# RedBot_Accelerometer.net
KiCad netlist of a schematic drawn in EAGLE
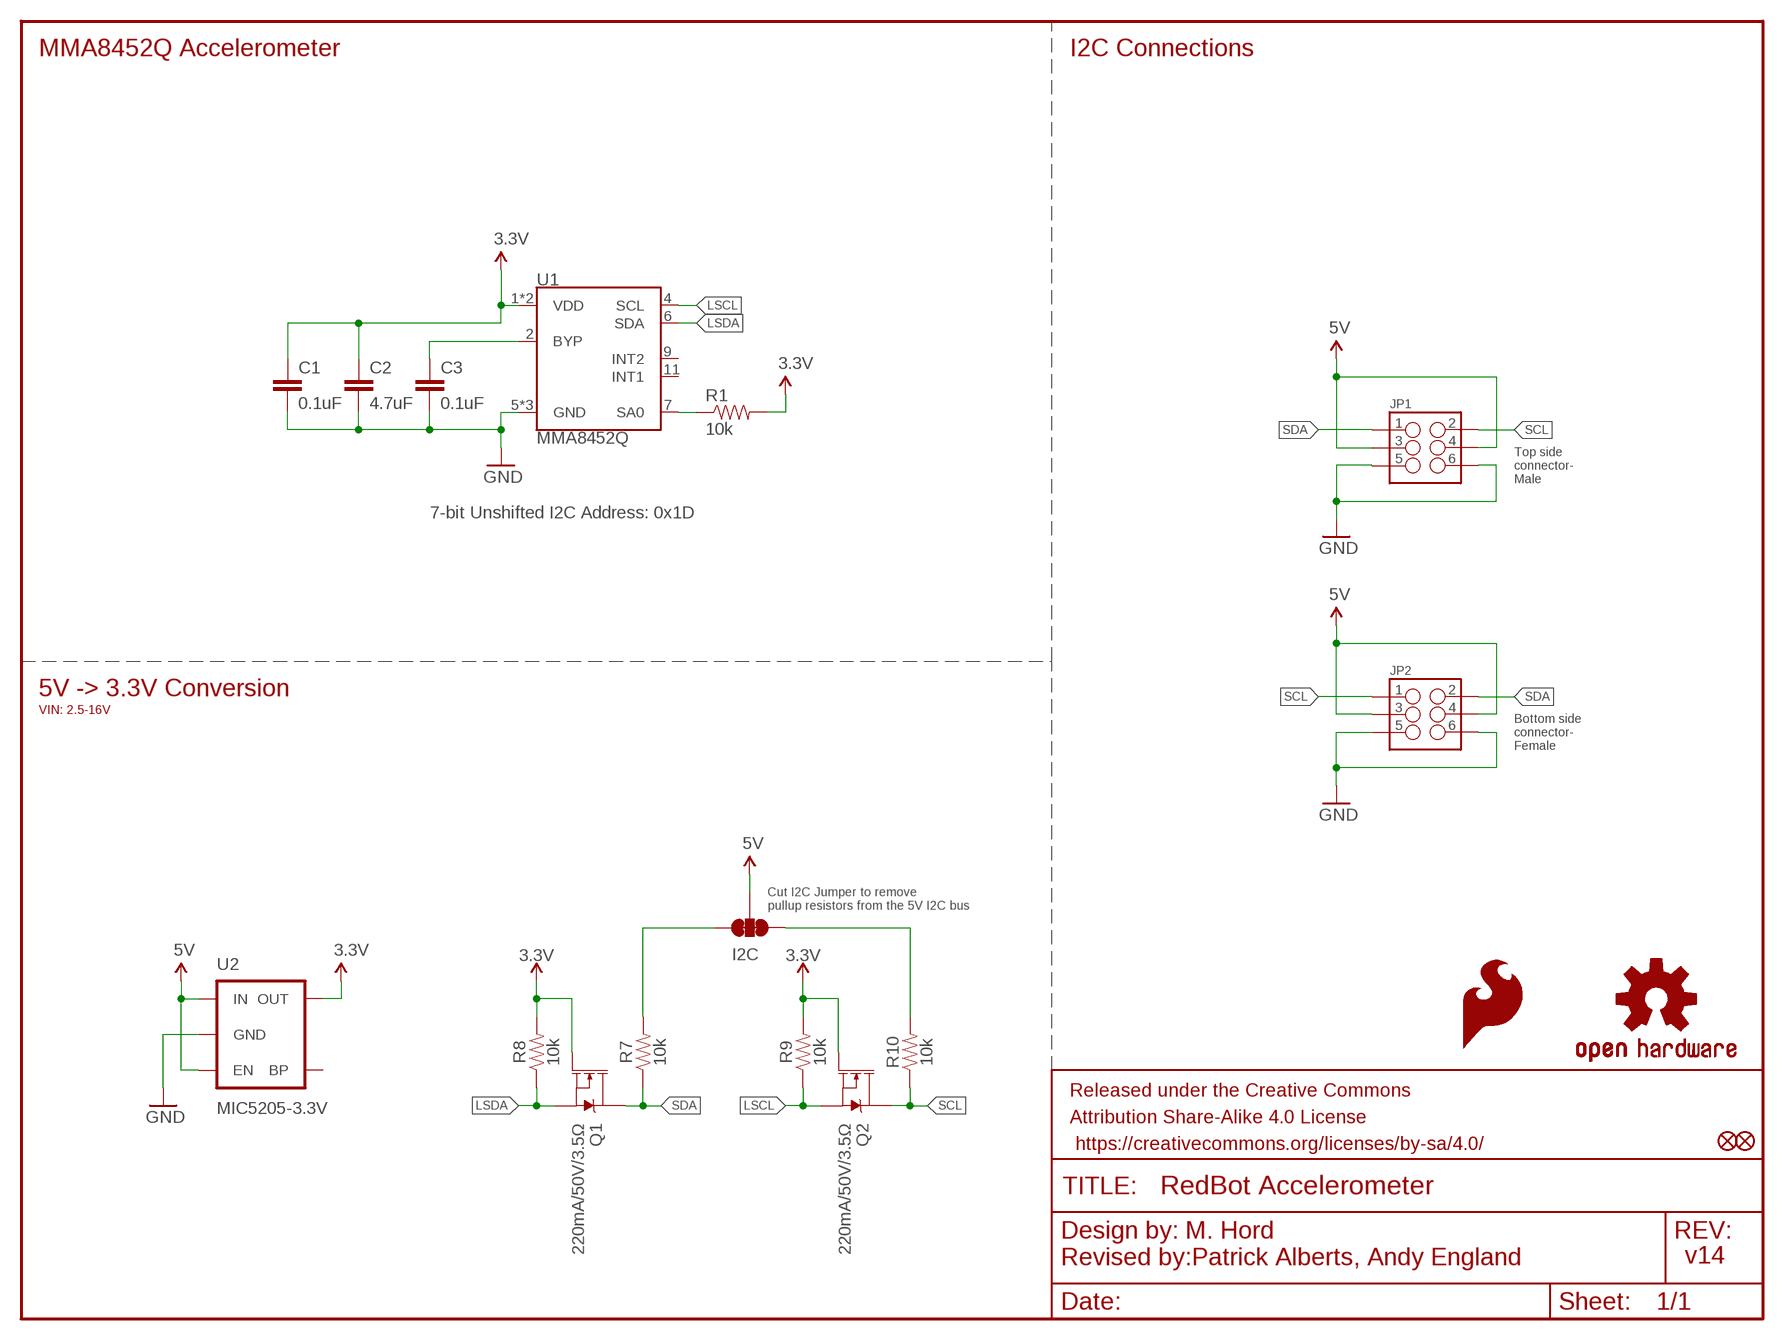
[diagram p0: schematic, sheet 1]

(export (version "E")
  (design (tool "Eeschema 10.0.6"))
  (components
    (comp (ref "C1")
      (value "0.1uF")
      (footprint "eagle-import:0603")
      (libsource (lib "eagle-import") (part "0.1UF-0603-25V-(+80/-20%)"))
    )
    (comp (ref "C2")
      (value "4.7uF")
      (footprint "eagle-import:0603")
      (libsource (lib "eagle-import") (part "4.7UF-0603-6.3V-(10%)"))
    )
    (comp (ref "C3")
      (value "0.1uF")
      (footprint "eagle-import:0603")
      (libsource (lib "eagle-import") (part "0.1UF-0603-25V-(+80/-20%)"))
    )
    (comp (ref "FID1")
      (value "FIDUCIAL1X2")
      (footprint "eagle-import:FIDUCIAL-1X2")
      (libsource (lib "eagle-import") (part "FIDUCIAL1X2"))
    )
    (comp (ref "FID3")
      (value "FIDUCIAL1X2")
      (footprint "eagle-import:FIDUCIAL-1X2")
      (libsource (lib "eagle-import") (part "FIDUCIAL1X2"))
    )
    (comp (ref "FRAME1")
      (value "FRAME-LETTER")
      (footprint "eagle-import:CREATIVE_COMMONS")
      (libsource (lib "eagle-import") (part "FRAME-LETTER"))
    )
    (comp (ref "I2C")
      (value "JUMPER-SMT_3_2-NC_TRACE_SILK")
      (footprint "eagle-import:SMT-JUMPER_3_2-NC_TRACE_SILK")
      (libsource (lib "eagle-import") (part "JUMPER-SMT_3_2-NC_TRACE_SILK"))
    )
    (comp (ref "JP1")
      (value "M03X2SMT")
      (footprint "eagle-import:2X3_SMT_POSTS")
      (libsource (lib "eagle-import") (part "M03X2SMT"))
    )
    (comp (ref "JP2")
      (value "M03X2FEMALE_SMD")
      (footprint "eagle-import:2X3_SMD")
      (libsource (lib "eagle-import") (part "M03X2FEMALE_SMD"))
    )
    (comp (ref "LOGO2")
      (value "OSHW-LOGOS")
      (footprint "eagle-import:OSHW-LOGO-S")
      (libsource (lib "eagle-import") (part "OSHW-LOGOS"))
    )
    (comp (ref "LOGO4")
      (value "SFE_LOGO_FLAME.1_INCH")
      (footprint "eagle-import:SFE_LOGO_FLAME_.1")
      (libsource (lib "eagle-import") (part "SFE_LOGO_FLAME.1_INCH"))
    )
    (comp (ref "Q1")
      (value "220mA/50V/3.5Ω")
      (footprint "eagle-import:SOT23-3")
      (libsource (lib "eagle-import") (part "MOSFET-NCH-BSS138"))
    )
    (comp (ref "Q2")
      (value "220mA/50V/3.5Ω")
      (footprint "eagle-import:SOT23-3")
      (libsource (lib "eagle-import") (part "MOSFET-NCH-BSS138"))
    )
    (comp (ref "R1")
      (value "10k")
      (footprint "eagle-import:0603")
      (libsource (lib "eagle-import") (part "10KOHM-0603-1/10W-1%"))
    )
    (comp (ref "R7")
      (value "10k")
      (footprint "eagle-import:0603")
      (libsource (lib "eagle-import") (part "10KOHM-0603-1/10W-1%"))
    )
    (comp (ref "R8")
      (value "10k")
      (footprint "eagle-import:0603")
      (libsource (lib "eagle-import") (part "10KOHM-0603-1/10W-1%"))
    )
    (comp (ref "R9")
      (value "10k")
      (footprint "eagle-import:0603")
      (libsource (lib "eagle-import") (part "10KOHM-0603-1/10W-1%"))
    )
    (comp (ref "R10")
      (value "10k")
      (footprint "eagle-import:0603")
      (libsource (lib "eagle-import") (part "10KOHM-0603-1/10W-1%"))
    )
    (comp (ref "U1")
      (value "MMA8452Q")
      (footprint "eagle-import:QFN-16")
      (libsource (lib "eagle-import") (part "MMA8452Q"))
    )
    (comp (ref "U2")
      (value "MIC5205-3.3V")
      (footprint "eagle-import:SOT23-5")
      (libsource (lib "eagle-import") (part "MIC52053.3V"))
    )
  )
  (nets
    (net (code "1") (name "3.3V") (class "Default")
      (node (ref "C1") (pin "1") (pinfunction "1_1") (pintype "passive"))
      (node (ref "C2") (pin "1") (pinfunction "1_1") (pintype "passive"))
      (node (ref "Q1") (pin "1") (pinfunction "G_1") (pintype "bidirectional"))
      (node (ref "Q2") (pin "1") (pinfunction "G_1") (pintype "bidirectional"))
      (node (ref "R1") (pin "2") (pinfunction "2_2") (pintype "passive"))
      (node (ref "R8") (pin "2") (pinfunction "2_2") (pintype "passive"))
      (node (ref "R9") (pin "2") (pinfunction "2_2") (pintype "passive"))
      (node (ref "U1") (pin "1") (pinfunction "VDD_1") (pintype "bidirectional"))
      (node (ref "U1") (pin "14") (pinfunction "VDD_14") (pintype "bidirectional"))
      (node (ref "U2") (pin "5") (pinfunction "OUT_5") (pintype "passive"))
    )
    (net (code "2") (name "5V") (class "Default")
      (node (ref "I2C") (pin "2") (pinfunction "2_2") (pintype "passive"))
      (node (ref "JP1") (pin "3") (pinfunction "3_3") (pintype "bidirectional"))
      (node (ref "JP1") (pin "4") (pinfunction "4_4") (pintype "bidirectional"))
      (node (ref "JP2") (pin "3") (pinfunction "3_3") (pintype "bidirectional"))
      (node (ref "JP2") (pin "4") (pinfunction "4_4") (pintype "bidirectional"))
      (node (ref "U2") (pin "1") (pinfunction "IN_1") (pintype "input"))
      (node (ref "U2") (pin "3") (pinfunction "EN_3") (pintype "input"))
    )
    (net (code "3") (name "GND") (class "Default")
      (node (ref "C1") (pin "2") (pinfunction "2_2") (pintype "passive"))
      (node (ref "C2") (pin "2") (pinfunction "2_2") (pintype "passive"))
      (node (ref "C3") (pin "2") (pinfunction "2_2") (pintype "passive"))
      (node (ref "JP1") (pin "5") (pinfunction "5_5") (pintype "bidirectional"))
      (node (ref "JP1") (pin "6") (pinfunction "6_6") (pintype "bidirectional"))
      (node (ref "JP2") (pin "5") (pinfunction "5_5") (pintype "bidirectional"))
      (node (ref "JP2") (pin "6") (pinfunction "6_6") (pintype "bidirectional"))
      (node (ref "U1") (pin "10") (pinfunction "GND_10") (pintype "bidirectional"))
      (node (ref "U1") (pin "12") (pinfunction "GND_12") (pintype "bidirectional"))
      (node (ref "U1") (pin "5") (pinfunction "GND_5") (pintype "bidirectional"))
      (node (ref "U2") (pin "2") (pinfunction "GND_2") (pintype "input"))
    )
    (net (code "4") (name "LSCL") (class "Default")
      (node (ref "Q2") (pin "2") (pinfunction "S_2") (pintype "bidirectional"))
      (node (ref "R9") (pin "1") (pinfunction "1_1") (pintype "passive"))
      (node (ref "U1") (pin "4") (pinfunction "SCL_4") (pintype "bidirectional"))
    )
    (net (code "5") (name "LSDA") (class "Default")
      (node (ref "Q1") (pin "2") (pinfunction "S_2") (pintype "bidirectional"))
      (node (ref "R8") (pin "1") (pinfunction "1_1") (pintype "passive"))
      (node (ref "U1") (pin "6") (pinfunction "SDA_6") (pintype "bidirectional"))
    )
    (net (code "6") (name "Net-(I2C-Pad1)") (class "Default")
      (node (ref "I2C") (pin "1") (pinfunction "1_1") (pintype "passive"))
      (node (ref "R10") (pin "2") (pinfunction "2_2") (pintype "passive"))
    )
    (net (code "7") (name "Net-(I2C-Pad3)") (class "Default")
      (node (ref "I2C") (pin "3") (pinfunction "3_3") (pintype "passive"))
      (node (ref "R7") (pin "2") (pinfunction "2_2") (pintype "passive"))
    )
    (net (code "8") (name "Net-(U1-BYP)") (class "Default")
      (node (ref "C3") (pin "1") (pinfunction "1_1") (pintype "passive"))
      (node (ref "U1") (pin "2") (pinfunction "BYP_2") (pintype "bidirectional"))
    )
    (net (code "9") (name "Net-(U1-SA0)") (class "Default")
      (node (ref "R1") (pin "1") (pinfunction "1_1") (pintype "passive"))
      (node (ref "U1") (pin "7") (pinfunction "SA0_7") (pintype "bidirectional"))
    )
    (net (code "10") (name "SCL") (class "Default")
      (node (ref "JP1") (pin "2") (pinfunction "2_2") (pintype "bidirectional"))
      (node (ref "JP2") (pin "1") (pinfunction "1_1") (pintype "bidirectional"))
      (node (ref "Q2") (pin "3") (pinfunction "D_3") (pintype "bidirectional"))
      (node (ref "R10") (pin "1") (pinfunction "1_1") (pintype "passive"))
    )
    (net (code "11") (name "SDA") (class "Default")
      (node (ref "JP1") (pin "1") (pinfunction "1_1") (pintype "bidirectional"))
      (node (ref "JP2") (pin "2") (pinfunction "2_2") (pintype "bidirectional"))
      (node (ref "Q1") (pin "3") (pinfunction "D_3") (pintype "bidirectional"))
      (node (ref "R7") (pin "1") (pinfunction "1_1") (pintype "passive"))
    )
    (net (code "12") (name "unconnected-(U1-INT1-Pad11)") (class "Default")
      (node (ref "U1") (pin "11") (pinfunction "INT1_11") (pintype "bidirectional"))
    )
    (net (code "13") (name "unconnected-(U1-INT2-Pad9)") (class "Default")
      (node (ref "U1") (pin "9") (pinfunction "INT2_9") (pintype "bidirectional"))
    )
    (net (code "14") (name "unconnected-(U2-BP-Pad4)") (class "Default")
      (node (ref "U2") (pin "4") (pinfunction "BP_4") (pintype "input"))
    )
  )
)
